# RS485.net
KiCad netlist of a schematic drawn in Altium Designer
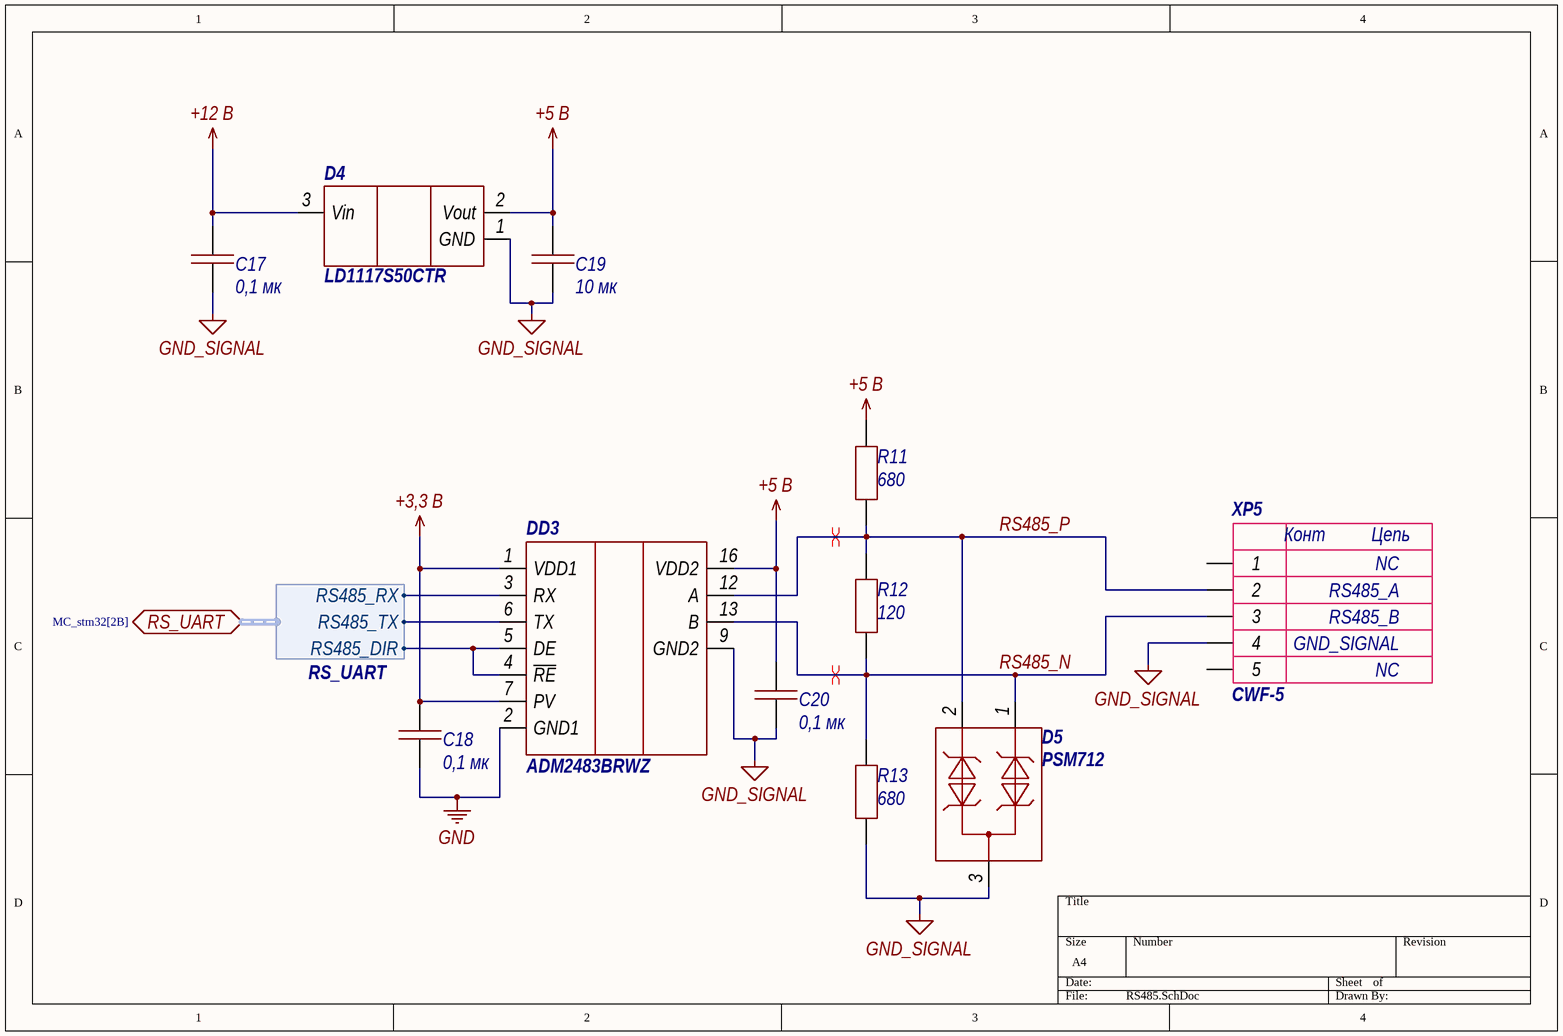
[diagram p0: RS485.SchDoc]

(export (version "E")
  (design (tool "Eeschema 10.0.6"))
  (components
    (comp (ref "C17")
      (value "0,1 мк")
      (footprint "0603C")
      (description "Конденсатор")
      (fields (field (name "PART NUMBER") "Capacitor_0,1u_10_50V_X7R_0603C") (field (name "TOLERANCE") "0,1"))
      (libsource (lib "Hydrolib") (part "Capacitor"))
    )
    (comp (ref "C18")
      (value "0,1 мк")
      (footprint "0603C")
      (description "Конденсатор")
      (fields (field (name "PART NUMBER") "Capacitor_0,1u_10_50V_X7R_0603C") (field (name "TOLERANCE") "0,1"))
      (libsource (lib "Hydrolib") (part "Capacitor"))
    )
    (comp (ref "C19")
      (value "10 мк")
      (footprint "1210C")
      (description "Конденсатор")
      (fields (field (name "PART NUMBER") "Capacitor_10u_10_35V_X7R_1210C") (field (name "TOLERANCE") "0,1"))
      (libsource (lib "Hydrolib") (part "Capacitor"))
    )
    (comp (ref "C20")
      (value "0,1 мк")
      (footprint "0603C")
      (description "Конденсатор")
      (fields (field (name "PART NUMBER") "Capacitor_0,1u_10_50V_X7R_0603C") (field (name "TOLERANCE") "0,1"))
      (libsource (lib "Hydrolib") (part "Capacitor"))
    )
    (comp (ref "D4")
      (value "LD1117S50CTR")
      (footprint "SOT223")
      (description "Линейный стабилизатор напряжения")
      (libsource (lib "Hydrolib") (part "LD1117S50CTR"))
    )
    (comp (ref "D5")
      (value "PSM712")
      (footprint "SOT23-3")
      (description "Защитный диод для линии RS-485")
      (libsource (lib "Hydrolib") (part "TVS_2_2dir"))
    )
    (comp (ref "DD3")
      (value "ADM2483BRWZ")
      (footprint "SOIC-16W")
      (description "Прием передатчик RS485 с гальванической развязкой")
      (libsource (lib "Hydrolib") (part "ADM2483BRWZ"))
    )
    (comp (ref "R11")
      (value "680")
      (footprint "0603R")
      (description "Резистор номиналом 680 Ом и точностью 1%")
      (fields (field (name "PART NUMBER") "Resistor_680_1_0603") (field (name "TOLERANCE") "1%"))
      (libsource (lib "Hydrolib") (part "Resistor"))
    )
    (comp (ref "R12")
      (value "120")
      (footprint "1206R")
      (description "Резистор номиналом 120 Ом и точностью 1%")
      (fields (field (name "PART NUMBER") "Resistor_120_1_0603") (field (name "TOLERANCE") "1%"))
      (libsource (lib "Hydrolib") (part "Resistor"))
    )
    (comp (ref "R13")
      (value "680")
      (footprint "0603R")
      (description "Резистор номиналом 680 Ом и точностью 1%")
      (fields (field (name "PART NUMBER") "Resistor_680_1_0603") (field (name "TOLERANCE") "1%"))
      (libsource (lib "Hydrolib") (part "Resistor"))
    )
    (comp (ref "XP5")
      (value "CWF-5")
      (footprint "CWF-5")
      (description "5-пиновый разъем с ключом")
      (fields
        (field (name "VALUE1") "NC")
        (field (name "VALUE2") "RS485_A")
        (field (name "VALUE3") "RS485_B")
        (field (name "VALUE4") "GND_SIGNAL")
        (field (name "VALUE5") "NC")
      )
      (libsource (lib "Hydrolib") (part "Conn_5pin"))
    )
  )
  (nets
    (net (code "2") (name "+3,3 В") (class "Default")
      (node (ref "C18") (pin "2") (pinfunction "2_2") (pintype "passive"))
      (node (ref "DD3") (pin "1") (pinfunction "VDD1_1") (pintype "passive"))
      (node (ref "DD3") (pin "7") (pinfunction "PV_7") (pintype "passive"))
    )
    (net (code "3") (name "+5 В") (class "Default")
      (node (ref "C19") (pin "2") (pinfunction "2_2") (pintype "passive"))
      (node (ref "C20") (pin "2") (pinfunction "2_2") (pintype "passive"))
      (node (ref "D4") (pin "2") (pinfunction "Vout_2") (pintype "passive"))
      (node (ref "DD3") (pin "16") (pinfunction "VDD2_16") (pintype "passive"))
      (node (ref "R11") (pin "1") (pinfunction "1_1") (pintype "passive"))
    )
    (net (code "4") (name "+12 В") (class "Default")
      (node (ref "C17") (pin "2") (pinfunction "2_2") (pintype "passive"))
      (node (ref "D4") (pin "3") (pinfunction "Vin_3") (pintype "passive"))
    )
    (net (code "5") (name "/RS485_DIR") (class "Default")
      (node (ref "DD3") (pin "4") (pinfunction "~{RE}_4") (pintype "passive"))
      (node (ref "DD3") (pin "5") (pinfunction "DE_5") (pintype "passive"))
    )
    (net (code "6") (name "/RS485_N") (class "Default")
      (node (ref "D5") (pin "1") (pinfunction "14_1") (pintype "passive"))
      (node (ref "DD3") (pin "13") (pinfunction "B_13") (pintype "passive"))
      (node (ref "R12") (pin "2") (pinfunction "2_2") (pintype "passive"))
      (node (ref "R13") (pin "1") (pinfunction "1_1") (pintype "passive"))
      (node (ref "XP5") (pin "3") (pinfunction "3_3") (pintype "passive"))
    )
    (net (code "7") (name "/RS485_P") (class "Default")
      (node (ref "D5") (pin "2") (pinfunction "15_2") (pintype "passive"))
      (node (ref "DD3") (pin "12") (pinfunction "A_12") (pintype "passive"))
      (node (ref "R11") (pin "2") (pinfunction "2_2") (pintype "passive"))
      (node (ref "R12") (pin "1") (pinfunction "1_1") (pintype "passive"))
      (node (ref "XP5") (pin "2") (pinfunction "2_2") (pintype "passive"))
    )
    (net (code "8") (name "/RS485_RX") (class "Default")
      (node (ref "DD3") (pin "3") (pinfunction "RX_3") (pintype "passive"))
    )
    (net (code "9") (name "/RS485_TX") (class "Default")
      (node (ref "DD3") (pin "6") (pinfunction "TX_6") (pintype "passive"))
    )
    (net (code "11") (name "GND") (class "Default")
      (node (ref "C18") (pin "1") (pinfunction "1_1") (pintype "passive"))
      (node (ref "DD3") (pin "2") (pinfunction "GND1_2") (pintype "passive"))
    )
    (net (code "12") (name "GND_SIGNAL") (class "Default")
      (node (ref "C17") (pin "1") (pinfunction "1_1") (pintype "passive"))
      (node (ref "C19") (pin "1") (pinfunction "1_1") (pintype "passive"))
      (node (ref "C20") (pin "1") (pinfunction "1_1") (pintype "passive"))
      (node (ref "D4") (pin "1") (pinfunction "GND_1") (pintype "passive"))
      (node (ref "D5") (pin "3") (pinfunction "16_3") (pintype "passive"))
      (node (ref "DD3") (pin "9") (pinfunction "GND2_9") (pintype "passive"))
      (node (ref "R13") (pin "2") (pinfunction "2_2") (pintype "passive"))
      (node (ref "XP5") (pin "4") (pinfunction "4_4") (pintype "passive"))
    )
    (net (code "13") (name "unconnected-(XP5-Pad1)") (class "Default")
      (node (ref "XP5") (pin "1") (pinfunction "1_1") (pintype "passive"))
    )
    (net (code "14") (name "unconnected-(XP5-Pad5)") (class "Default")
      (node (ref "XP5") (pin "5") (pinfunction "5_5") (pintype "passive"))
    )
  )
)
